# 04_-_Mechanicals_and_Connectors.net
KiCad netlist of a schematic drawn in Altium Designer
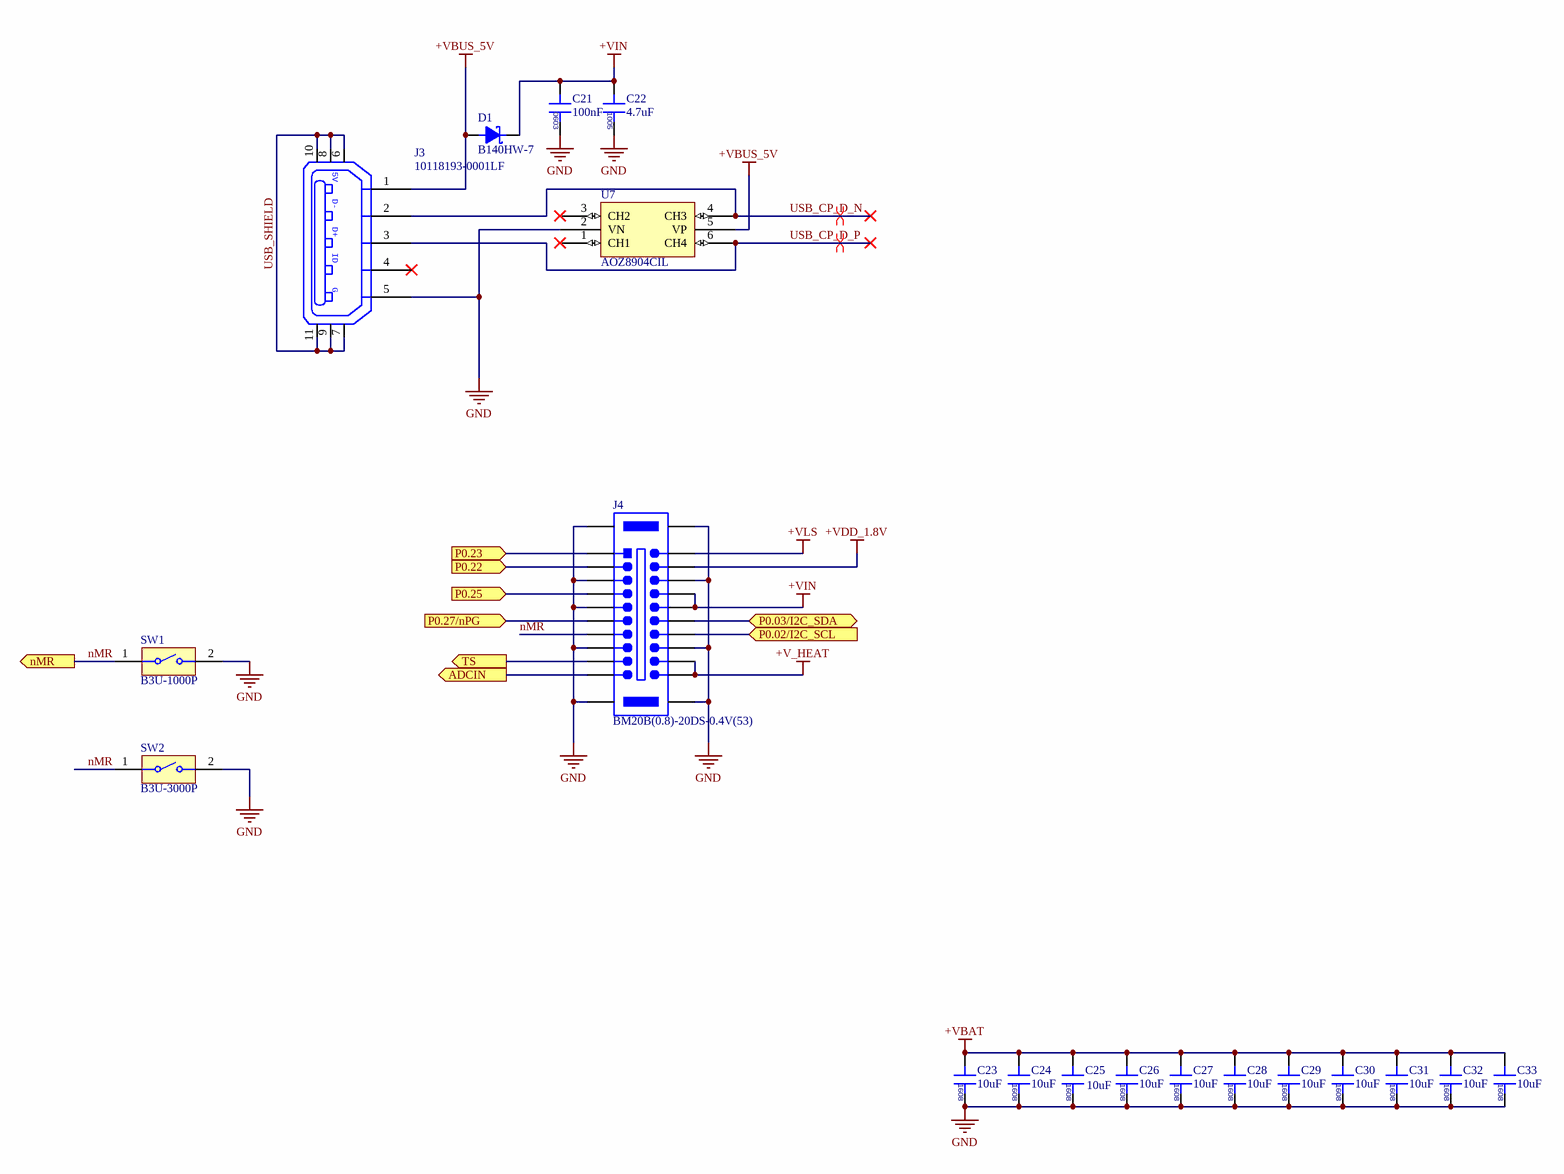
[diagram p0: [04] - Mechanicals and Connectors.SchDoc]

(export (version "E")
  (design (tool "Eeschema 10.0.6"))
  (components
    (comp (ref "C21")
      (value "100nF")
      (footprint "CAPC0603X03N")
      (description "CAP CER 0.1UF 16V X7S 0201")
      (fields
        (field (name "MANUFACTURER") "Murata")
        (field (name "MANUFACTURER PART NUMBER") "GRM033C71C104ME14D")
      )
      (libsource (lib "Schlib-master") (part "GRM033C71C104ME14D"))
    )
    (comp (ref "C22")
      (value "4.7uF")
      (footprint "CAPC1005X06N")
      (description "CAP CER 4.7UF 16V X5R 0402")
      (fields (field (name "TOLERANCE") "20%") (field (name "MANUFACTURER") "Samsung"))
      (libsource (lib "Schlib-master") (part "CL05A475MO5NUNC"))
    )
    (comp (ref "C23")
      (value "10uF")
      (footprint "CAPC1608X08N")
      (description "CAP CER 10UF 16V X6S 0603")
      (fields
        (field (name "MANUFACTURER") "Samsung")
        (field (name "MANUFACTURER PART NUMBER") "CL10X106MO8NRNC")
      )
      (libsource (lib "Schlib-master") (part "CL10X106MO8NRNC"))
    )
    (comp (ref "C24")
      (value "10uF")
      (footprint "CAPC1608X08N")
      (description "CAP CER 10UF 16V X6S 0603")
      (fields
        (field (name "MANUFACTURER") "Samsung")
        (field (name "MANUFACTURER PART NUMBER") "CL10X106MO8NRNC")
      )
      (libsource (lib "Schlib-master") (part "CL10X106MO8NRNC"))
    )
    (comp (ref "C25")
      (value "10uF")
      (footprint "CAPC1608X08N")
      (description "CAP CER 10UF 16V X6S 0603")
      (fields
        (field (name "MANUFACTURER") "Samsung")
        (field (name "MANUFACTURER PART NUMBER") "CL10X106MO8NRNC")
      )
      (libsource (lib "Schlib-master") (part "CL10X106MO8NRNC"))
    )
    (comp (ref "C26")
      (value "10uF")
      (footprint "CAPC1608X08N")
      (description "CAP CER 10UF 16V X6S 0603")
      (fields
        (field (name "MANUFACTURER") "Samsung")
        (field (name "MANUFACTURER PART NUMBER") "CL10X106MO8NRNC")
      )
      (libsource (lib "Schlib-master") (part "CL10X106MO8NRNC"))
    )
    (comp (ref "C27")
      (value "10uF")
      (footprint "CAPC1608X08N")
      (description "CAP CER 10UF 16V X6S 0603")
      (fields
        (field (name "MANUFACTURER") "Samsung")
        (field (name "MANUFACTURER PART NUMBER") "CL10X106MO8NRNC")
      )
      (libsource (lib "Schlib-master") (part "CL10X106MO8NRNC"))
    )
    (comp (ref "C28")
      (value "10uF")
      (footprint "CAPC1608X08N")
      (description "CAP CER 10UF 16V X6S 0603")
      (fields
        (field (name "MANUFACTURER") "Samsung")
        (field (name "MANUFACTURER PART NUMBER") "CL10X106MO8NRNC")
      )
      (libsource (lib "Schlib-master") (part "CL10X106MO8NRNC"))
    )
    (comp (ref "C29")
      (value "10uF")
      (footprint "CAPC1608X08N")
      (description "CAP CER 10UF 16V X6S 0603")
      (fields
        (field (name "MANUFACTURER") "Samsung")
        (field (name "MANUFACTURER PART NUMBER") "CL10X106MO8NRNC")
      )
      (libsource (lib "Schlib-master") (part "CL10X106MO8NRNC"))
    )
    (comp (ref "C30")
      (value "10uF")
      (footprint "CAPC1608X08N")
      (description "CAP CER 10UF 16V X6S 0603")
      (fields
        (field (name "MANUFACTURER") "Samsung")
        (field (name "MANUFACTURER PART NUMBER") "CL10X106MO8NRNC")
      )
      (libsource (lib "Schlib-master") (part "CL10X106MO8NRNC"))
    )
    (comp (ref "C31")
      (value "10uF")
      (footprint "CAPC1608X08N")
      (description "CAP CER 10UF 16V X6S 0603")
      (fields
        (field (name "MANUFACTURER") "Samsung")
        (field (name "MANUFACTURER PART NUMBER") "CL10X106MO8NRNC")
      )
      (libsource (lib "Schlib-master") (part "CL10X106MO8NRNC"))
    )
    (comp (ref "C32")
      (value "10uF")
      (footprint "CAPC1608X08N")
      (description "CAP CER 10UF 16V X6S 0603")
      (fields
        (field (name "MANUFACTURER") "Samsung")
        (field (name "MANUFACTURER PART NUMBER") "CL10X106MO8NRNC")
      )
      (libsource (lib "Schlib-master") (part "CL10X106MO8NRNC"))
    )
    (comp (ref "C33")
      (value "10uF")
      (footprint "CAPC1608X08N")
      (description "CAP CER 10UF 16V X6S 0603")
      (fields
        (field (name "MANUFACTURER") "Samsung")
        (field (name "MANUFACTURER PART NUMBER") "CL10X106MO8NRNC")
      )
      (libsource (lib "Schlib-master") (part "CL10X106MO8NRNC"))
    )
    (comp (ref "D1")
      (value "B140HW-7")
      (footprint "SOD-123")
      (description "Diode Schottky 40V 1A 2Pin SOD123")
      (fields (field (name "MANUFACTURER") "Diodes"))
      (libsource (lib "Schlib-master") (part "B140HW-7"))
    )
    (comp (ref "J3")
      (value "10118193-0001LF")
      (footprint "10118193")
      (description "CONN USB MICRO B RECPT SMT R/A")
      (fields (field (name "MANUFACTURER") "FCI"))
      (libsource (lib "Schlib-master") (part "10118193-0001LF"))
    )
    (comp (ref "J4")
      (value "BM20B(0.8)-20DS-0.4V(53)")
      (footprint "BM20B(0.8)-20DS-0.4V(53)")
      (description "CONN RCPT 20POS 0.4MM SMD")
      (fields (field (name "MANUFACTURER") "Hirose"))
      (libsource (lib "Schlib-master") (part "BM20B(0.8)-20DS-0.4V(53)"))
    )
    (comp (ref "SW1")
      (value "B3U-1000P")
      (footprint "B3U-1000P")
      (description "SWITCH TACTILE SPST-NO 0.05A 12V")
      (fields (field (name "MANUFACTURER") "Omron"))
      (libsource (lib "Schlib-master") (part "B3U-1000P"))
    )
    (comp (ref "SW2")
      (value "B3U-3000P")
      (footprint "B3U-3000P")
      (description "SWITCH TACTILE SPST-NO 0.05A 12V")
      (fields (field (name "MANUFACTURER") "Omron"))
      (libsource (lib "Schlib-master") (part "B3U-3000P"))
    )
    (comp (ref "U7")
      (value "AOZ8904CIL")
      (footprint "SOT95P280X145-6N")
      (description "TVS DIODE 5.5VWM 18VC SOT23-6")
      (fields (field (name "MANUFACTURER") "Alpha & Omega Semiconductor"))
      (libsource (lib "Schlib-master") (part "AOZ8904CIL"))
    )
  )
  (nets
    (net (code "1") (name "+VBAT") (class "Default")
      (node (ref "C23") (pin "2") (pinfunction "2_2") (pintype "passive"))
      (node (ref "C24") (pin "2") (pinfunction "2_2") (pintype "passive"))
      (node (ref "C25") (pin "2") (pinfunction "2_2") (pintype "passive"))
      (node (ref "C26") (pin "2") (pinfunction "2_2") (pintype "passive"))
      (node (ref "C27") (pin "2") (pinfunction "2_2") (pintype "passive"))
      (node (ref "C28") (pin "2") (pinfunction "2_2") (pintype "passive"))
      (node (ref "C29") (pin "2") (pinfunction "2_2") (pintype "passive"))
      (node (ref "C30") (pin "2") (pinfunction "2_2") (pintype "passive"))
      (node (ref "C31") (pin "2") (pinfunction "2_2") (pintype "passive"))
      (node (ref "C32") (pin "2") (pinfunction "2_2") (pintype "passive"))
      (node (ref "C33") (pin "2") (pinfunction "2_2") (pintype "passive"))
    )
    (net (code "2") (name "+VBUS_5V") (class "Default")
      (node (ref "D1") (pin "2") (pinfunction "Anode_2") (pintype "passive"))
      (node (ref "J3") (pin "1") (pinfunction "P1_1") (pintype "passive"))
      (node (ref "U7") (pin "5") (pinfunction "VP_5") (pintype "power_in"))
    )
    (net (code "3") (name "+VDD_1.8V") (class "Default")
      (node (ref "J4") (pin "4") (pinfunction "4_4") (pintype "passive"))
    )
    (net (code "4") (name "+VIN") (class "Default")
      (node (ref "C21") (pin "2") (pinfunction "2_2") (pintype "passive"))
      (node (ref "C22") (pin "2") (pinfunction "2_2") (pintype "passive"))
      (node (ref "D1") (pin "1") (pinfunction "Cathode_1") (pintype "passive"))
      (node (ref "J4") (pin "10") (pinfunction "10_10") (pintype "passive"))
      (node (ref "J4") (pin "8") (pinfunction "8_8") (pintype "passive"))
    )
    (net (code "5") (name "+VLS") (class "Default")
      (node (ref "J4") (pin "2") (pinfunction "2_2") (pintype "passive"))
    )
    (net (code "6") (name "+V_HEAT") (class "Default")
      (node (ref "J4") (pin "18") (pinfunction "18_18") (pintype "passive"))
      (node (ref "J4") (pin "20") (pinfunction "20_20") (pintype "passive"))
    )
    (net (code "7") (name "/ADCIN") (class "Default")
      (node (ref "J4") (pin "19") (pinfunction "19_19") (pintype "passive"))
    )
    (net (code "8") (name "/P0.02{slash}I2C_SCL") (class "Default")
      (node (ref "J4") (pin "14") (pinfunction "14_14") (pintype "passive"))
    )
    (net (code "9") (name "/P0.03{slash}I2C_SDA") (class "Default")
      (node (ref "J4") (pin "12") (pinfunction "12_12") (pintype "passive"))
    )
    (net (code "10") (name "/P0.22") (class "Default")
      (node (ref "J4") (pin "3") (pinfunction "3_3") (pintype "passive"))
    )
    (net (code "11") (name "/P0.23") (class "Default")
      (node (ref "J4") (pin "1") (pinfunction "1_1") (pintype "passive"))
    )
    (net (code "12") (name "/P0.25") (class "Default")
      (node (ref "J4") (pin "7") (pinfunction "7_7") (pintype "passive"))
    )
    (net (code "13") (name "/P0.27{slash}nPG") (class "Default")
      (node (ref "J4") (pin "11") (pinfunction "11_11") (pintype "passive"))
    )
    (net (code "14") (name "/TS") (class "Default")
      (node (ref "J4") (pin "17") (pinfunction "17_17") (pintype "passive"))
    )
    (net (code "15") (name "/USB_CP_D_N") (class "Default")
      (node (ref "J3") (pin "2") (pinfunction "P2_2") (pintype "passive"))
      (node (ref "U7") (pin "4") (pinfunction "CH3_4") (pintype "bidirectional"))
    )
    (net (code "16") (name "/USB_CP_D_P") (class "Default")
      (node (ref "J3") (pin "3") (pinfunction "P3_3") (pintype "passive"))
      (node (ref "U7") (pin "6") (pinfunction "CH4_6") (pintype "bidirectional"))
    )
    (net (code "17") (name "/USB_SHIELD") (class "Default")
      (node (ref "J3") (pin "10") (pinfunction "10_10") (pintype "passive"))
      (node (ref "J3") (pin "11") (pinfunction "11_11") (pintype "passive"))
      (node (ref "J3") (pin "6") (pinfunction "6_6") (pintype "passive"))
      (node (ref "J3") (pin "7") (pinfunction "7_7") (pintype "passive"))
      (node (ref "J3") (pin "8") (pinfunction "8_8") (pintype "passive"))
      (node (ref "J3") (pin "9") (pinfunction "9_9") (pintype "passive"))
    )
    (net (code "18") (name "/nMR") (class "Default")
      (node (ref "J4") (pin "13") (pinfunction "13_13") (pintype "passive"))
      (node (ref "SW1") (pin "1") (pinfunction "1_1") (pintype "passive"))
      (node (ref "SW2") (pin "1") (pinfunction "1_1") (pintype "passive"))
    )
    (net (code "19") (name "GND") (class "Default")
      (node (ref "C21") (pin "1") (pinfunction "1_1") (pintype "passive"))
      (node (ref "C22") (pin "1") (pinfunction "1_1") (pintype "passive"))
      (node (ref "C23") (pin "1") (pinfunction "1_1") (pintype "passive"))
      (node (ref "C24") (pin "1") (pinfunction "1_1") (pintype "passive"))
      (node (ref "C25") (pin "1") (pinfunction "1_1") (pintype "passive"))
      (node (ref "C26") (pin "1") (pinfunction "1_1") (pintype "passive"))
      (node (ref "C27") (pin "1") (pinfunction "1_1") (pintype "passive"))
      (node (ref "C28") (pin "1") (pinfunction "1_1") (pintype "passive"))
      (node (ref "C29") (pin "1") (pinfunction "1_1") (pintype "passive"))
      (node (ref "C30") (pin "1") (pinfunction "1_1") (pintype "passive"))
      (node (ref "C31") (pin "1") (pinfunction "1_1") (pintype "passive"))
      (node (ref "C32") (pin "1") (pinfunction "1_1") (pintype "passive"))
      (node (ref "C33") (pin "1") (pinfunction "1_1") (pintype "passive"))
      (node (ref "J3") (pin "5") (pinfunction "P5_5") (pintype "passive"))
      (node (ref "J4") (pin "15") (pinfunction "15_15") (pintype "passive"))
      (node (ref "J4") (pin "16") (pinfunction "16_16") (pintype "passive"))
      (node (ref "J4") (pin "5") (pinfunction "5_5") (pintype "passive"))
      (node (ref "J4") (pin "6") (pinfunction "6_6") (pintype "passive"))
      (node (ref "J4") (pin "9") (pinfunction "9_9") (pintype "passive"))
      (node (ref "J4") (pin "SH1") (pinfunction "SH1_SH1") (pintype "passive"))
      (node (ref "J4") (pin "SH2") (pinfunction "SH2_SH2") (pintype "passive"))
      (node (ref "J4") (pin "SH3") (pinfunction "SH3_SH3") (pintype "passive"))
      (node (ref "J4") (pin "SH4") (pinfunction "SH4_SH4") (pintype "passive"))
      (node (ref "SW1") (pin "2") (pinfunction "2_2") (pintype "passive"))
      (node (ref "SW2") (pin "2") (pinfunction "2_2") (pintype "passive"))
      (node (ref "U7") (pin "2") (pinfunction "VN_2") (pintype "power_in"))
    )
    (net (code "20") (name "unconnected-(J3-P4-Pad4)") (class "Default")
      (node (ref "J3") (pin "4") (pinfunction "P4_4") (pintype "passive+no_connect"))
    )
    (net (code "21") (name "unconnected-(U7-CH1-Pad1)") (class "Default")
      (node (ref "U7") (pin "1") (pinfunction "CH1_1") (pintype "bidirectional+no_connect"))
    )
    (net (code "22") (name "unconnected-(U7-CH2-Pad3)") (class "Default")
      (node (ref "U7") (pin "3") (pinfunction "CH2_3") (pintype "bidirectional+no_connect"))
    )
  )
)
